# EMGPreamp_extRefv4.net
KiCad netlist of a schematic drawn in EAGLE
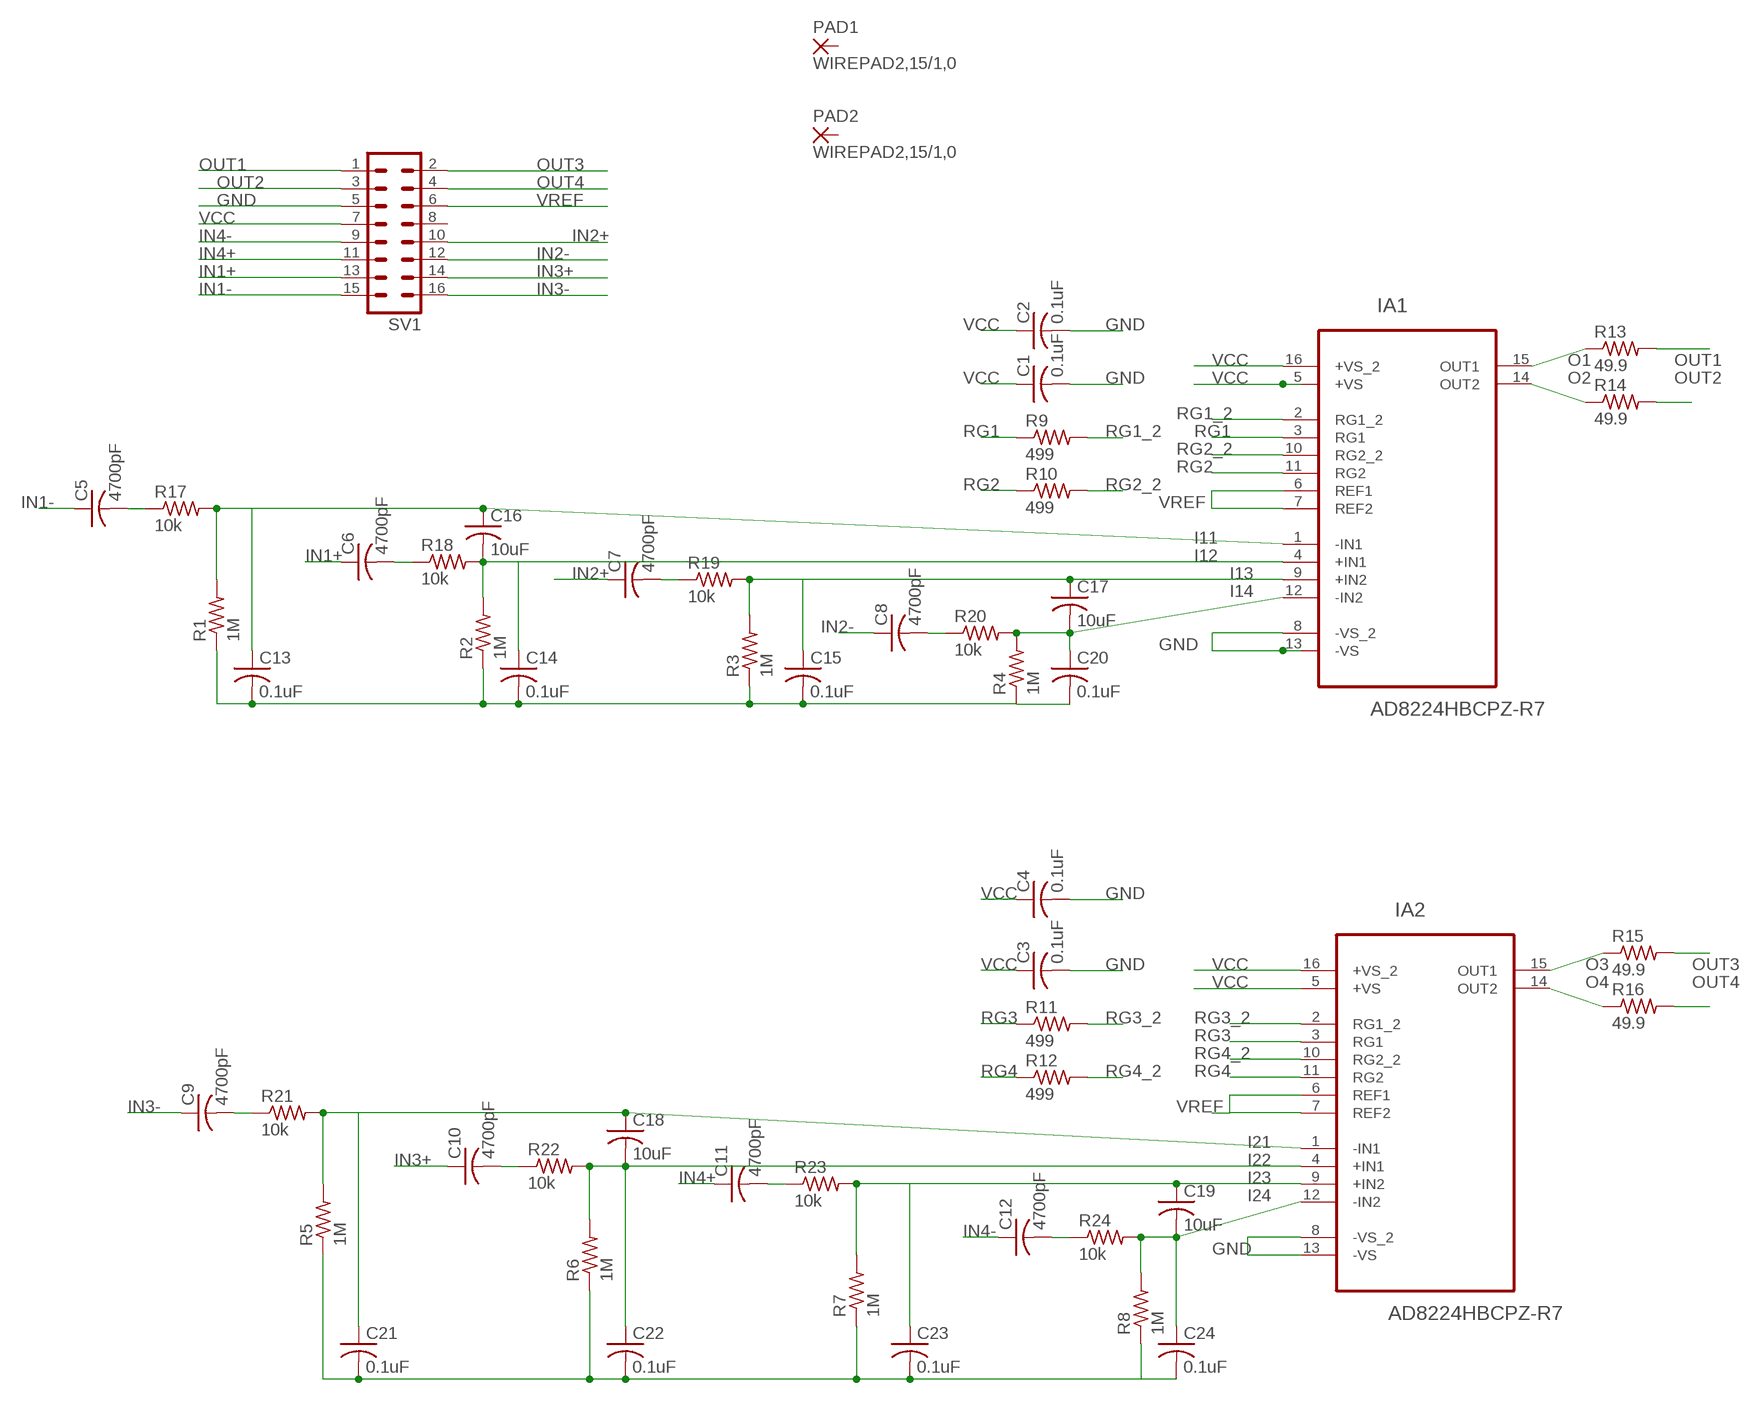
[diagram p0: schematic, sheet 1]

(export (version "E")
  (design (tool "Eeschema 10.0.6"))
  (components
    (comp (ref "C1")
      (value "0.1uF")
      (footprint "eagle-import:C0805")
      (libsource (lib "eagle-import") (part "C-USC0805"))
    )
    (comp (ref "C2")
      (value "0.1uF")
      (footprint "eagle-import:C0805")
      (libsource (lib "eagle-import") (part "C-USC0805"))
    )
    (comp (ref "C3")
      (value "0.1uF")
      (footprint "eagle-import:C0805")
      (libsource (lib "eagle-import") (part "C-USC0805"))
    )
    (comp (ref "C4")
      (value "0.1uF")
      (footprint "eagle-import:C0805")
      (libsource (lib "eagle-import") (part "C-USC0805"))
    )
    (comp (ref "C5")
      (value "4700pF")
      (footprint "eagle-import:C0805")
      (libsource (lib "eagle-import") (part "C-USC0805"))
    )
    (comp (ref "C6")
      (value "4700pF")
      (footprint "eagle-import:C0805")
      (libsource (lib "eagle-import") (part "C-USC0805"))
    )
    (comp (ref "C7")
      (value "4700pF")
      (footprint "eagle-import:C0805")
      (libsource (lib "eagle-import") (part "C-USC0805"))
    )
    (comp (ref "C8")
      (value "4700pF")
      (footprint "eagle-import:C0805")
      (libsource (lib "eagle-import") (part "C-USC0805"))
    )
    (comp (ref "C9")
      (value "4700pF")
      (footprint "eagle-import:C0805")
      (libsource (lib "eagle-import") (part "C-USC0805"))
    )
    (comp (ref "C10")
      (value "4700pF")
      (footprint "eagle-import:C0805")
      (libsource (lib "eagle-import") (part "C-USC0805"))
    )
    (comp (ref "C11")
      (value "4700pF")
      (footprint "eagle-import:C0805")
      (libsource (lib "eagle-import") (part "C-USC0805"))
    )
    (comp (ref "C12")
      (value "4700pF")
      (footprint "eagle-import:C0805")
      (libsource (lib "eagle-import") (part "C-USC0805"))
    )
    (comp (ref "C13")
      (value "0.1uF")
      (footprint "eagle-import:C0805")
      (libsource (lib "eagle-import") (part "C-USC0805"))
    )
    (comp (ref "C14")
      (value "0.1uF")
      (footprint "eagle-import:C0805")
      (libsource (lib "eagle-import") (part "C-USC0805"))
    )
    (comp (ref "C15")
      (value "0.1uF")
      (footprint "eagle-import:C0805")
      (libsource (lib "eagle-import") (part "C-USC0805"))
    )
    (comp (ref "C16")
      (value "10uF")
      (footprint "eagle-import:C0805")
      (libsource (lib "eagle-import") (part "resistor_C-USC0805"))
    )
    (comp (ref "C17")
      (value "10uF")
      (footprint "eagle-import:C0805")
      (libsource (lib "eagle-import") (part "resistor_C-USC0805"))
    )
    (comp (ref "C18")
      (value "10uF")
      (footprint "eagle-import:C0805")
      (libsource (lib "eagle-import") (part "resistor_C-USC0805"))
    )
    (comp (ref "C19")
      (value "10uF")
      (footprint "eagle-import:C0805")
      (libsource (lib "eagle-import") (part "resistor_C-USC0805"))
    )
    (comp (ref "C20")
      (value "0.1uF")
      (footprint "eagle-import:C0805")
      (libsource (lib "eagle-import") (part "C-USC0805"))
    )
    (comp (ref "C21")
      (value "0.1uF")
      (footprint "eagle-import:C0805")
      (libsource (lib "eagle-import") (part "C-USC0805"))
    )
    (comp (ref "C22")
      (value "0.1uF")
      (footprint "eagle-import:C0805")
      (libsource (lib "eagle-import") (part "C-USC0805"))
    )
    (comp (ref "C23")
      (value "0.1uF")
      (footprint "eagle-import:C0805")
      (libsource (lib "eagle-import") (part "C-USC0805"))
    )
    (comp (ref "C24")
      (value "0.1uF")
      (footprint "eagle-import:C0805")
      (libsource (lib "eagle-import") (part "C-USC0805"))
    )
    (comp (ref "IA1")
      (value "AD8224HBCPZ-R7")
      (footprint "eagle-import:QFN65P400X400X100-16N")
      (libsource (lib "eagle-import") (part "AD8224HBCPZ-R7"))
    )
    (comp (ref "IA2")
      (value "AD8224HBCPZ-R7")
      (footprint "eagle-import:QFN65P400X400X100-16N")
      (libsource (lib "eagle-import") (part "AD8224HBCPZ-R7"))
    )
    (comp (ref "PAD1")
      (value "WIREPAD2,15/1,0")
      (footprint "eagle-import:2,15_1,0")
      (libsource (lib "eagle-import") (part "WIREPAD2,15/1,0"))
    )
    (comp (ref "PAD2")
      (value "WIREPAD2,15/1,0")
      (footprint "eagle-import:2,15_1,0")
      (libsource (lib "eagle-import") (part "WIREPAD2,15/1,0"))
    )
    (comp (ref "R1")
      (value "1M")
      (footprint "eagle-import:R0805")
      (libsource (lib "eagle-import") (part "resistor_R-US_R0805"))
    )
    (comp (ref "R2")
      (value "1M")
      (footprint "eagle-import:R0805")
      (libsource (lib "eagle-import") (part "resistor_R-US_R0805"))
    )
    (comp (ref "R3")
      (value "1M")
      (footprint "eagle-import:R0805")
      (libsource (lib "eagle-import") (part "resistor_R-US_R0805"))
    )
    (comp (ref "R4")
      (value "1M")
      (footprint "eagle-import:R0805")
      (libsource (lib "eagle-import") (part "resistor_R-US_R0805"))
    )
    (comp (ref "R5")
      (value "1M")
      (footprint "eagle-import:R0805")
      (libsource (lib "eagle-import") (part "resistor_R-US_R0805"))
    )
    (comp (ref "R6")
      (value "1M")
      (footprint "eagle-import:R0805")
      (libsource (lib "eagle-import") (part "resistor_R-US_R0805"))
    )
    (comp (ref "R7")
      (value "1M")
      (footprint "eagle-import:R0805")
      (libsource (lib "eagle-import") (part "resistor_R-US_R0805"))
    )
    (comp (ref "R8")
      (value "1M")
      (footprint "eagle-import:R0805")
      (libsource (lib "eagle-import") (part "resistor_R-US_R0805"))
    )
    (comp (ref "R9")
      (value "499")
      (footprint "eagle-import:R0805")
      (libsource (lib "eagle-import") (part "R-US_R0805"))
    )
    (comp (ref "R10")
      (value "499")
      (footprint "eagle-import:R0805")
      (libsource (lib "eagle-import") (part "R-US_R0805"))
    )
    (comp (ref "R11")
      (value "499")
      (footprint "eagle-import:R0805")
      (libsource (lib "eagle-import") (part "R-US_R0805"))
    )
    (comp (ref "R12")
      (value "499")
      (footprint "eagle-import:R0805")
      (libsource (lib "eagle-import") (part "R-US_R0805"))
    )
    (comp (ref "R13")
      (value "49.9")
      (footprint "eagle-import:R0805")
      (libsource (lib "eagle-import") (part "R-US_R0805"))
    )
    (comp (ref "R14")
      (value "49.9")
      (footprint "eagle-import:R0805")
      (libsource (lib "eagle-import") (part "R-US_R0805"))
    )
    (comp (ref "R15")
      (value "49.9")
      (footprint "eagle-import:R0805")
      (libsource (lib "eagle-import") (part "R-US_R0805"))
    )
    (comp (ref "R16")
      (value "49.9")
      (footprint "eagle-import:R0805")
      (libsource (lib "eagle-import") (part "R-US_R0805"))
    )
    (comp (ref "R17")
      (value "10k")
      (footprint "eagle-import:R0805")
      (libsource (lib "eagle-import") (part "resistor_R-US_R0805"))
    )
    (comp (ref "R18")
      (value "10k")
      (footprint "eagle-import:R0805")
      (libsource (lib "eagle-import") (part "resistor_R-US_R0805"))
    )
    (comp (ref "R19")
      (value "10k")
      (footprint "eagle-import:R0805")
      (libsource (lib "eagle-import") (part "resistor_R-US_R0805"))
    )
    (comp (ref "R20")
      (value "10k")
      (footprint "eagle-import:R0805")
      (libsource (lib "eagle-import") (part "resistor_R-US_R0805"))
    )
    (comp (ref "R21")
      (value "10k")
      (footprint "eagle-import:R0805")
      (libsource (lib "eagle-import") (part "resistor_R-US_R0805"))
    )
    (comp (ref "R22")
      (value "10k")
      (footprint "eagle-import:R0805")
      (libsource (lib "eagle-import") (part "resistor_R-US_R0805"))
    )
    (comp (ref "R23")
      (value "10k")
      (footprint "eagle-import:R0805")
      (libsource (lib "eagle-import") (part "resistor_R-US_R0805"))
    )
    (comp (ref "R24")
      (value "10k")
      (footprint "eagle-import:R0805")
      (libsource (lib "eagle-import") (part "resistor_R-US_R0805"))
    )
    (comp (ref "SV1")
      (value "MA08-2W")
      (footprint "eagle-import:MA08-2W")
      (libsource (lib "eagle-import") (part "MA08-2W"))
    )
  )
  (nets
    (net (code "1") (name "/GND") (class "Default")
      (node (ref "C1") (pin "2") (pinfunction "2_2") (pintype "passive"))
      (node (ref "C13") (pin "2") (pinfunction "2_2") (pintype "passive"))
      (node (ref "C14") (pin "2") (pinfunction "2_2") (pintype "passive"))
      (node (ref "C15") (pin "2") (pinfunction "2_2") (pintype "passive"))
      (node (ref "C2") (pin "2") (pinfunction "2_2") (pintype "passive"))
      (node (ref "C20") (pin "2") (pinfunction "2_2") (pintype "passive"))
      (node (ref "C21") (pin "2") (pinfunction "2_2") (pintype "passive"))
      (node (ref "C22") (pin "2") (pinfunction "2_2") (pintype "passive"))
      (node (ref "C23") (pin "2") (pinfunction "2_2") (pintype "passive"))
      (node (ref "C24") (pin "2") (pinfunction "2_2") (pintype "passive"))
      (node (ref "C3") (pin "2") (pinfunction "2_2") (pintype "passive"))
      (node (ref "C4") (pin "2") (pinfunction "2_2") (pintype "passive"))
      (node (ref "IA1") (pin "13") (pinfunction "-VS_13") (pintype "power_in"))
      (node (ref "IA1") (pin "8") (pinfunction "-VS_2_8") (pintype "power_in"))
      (node (ref "IA2") (pin "13") (pinfunction "-VS_13") (pintype "power_in"))
      (node (ref "IA2") (pin "8") (pinfunction "-VS_2_8") (pintype "power_in"))
      (node (ref "R1") (pin "1") (pinfunction "1_1") (pintype "passive"))
      (node (ref "R2") (pin "1") (pinfunction "1_1") (pintype "passive"))
      (node (ref "R3") (pin "1") (pinfunction "1_1") (pintype "passive"))
      (node (ref "R4") (pin "1") (pinfunction "1_1") (pintype "passive"))
      (node (ref "R5") (pin "1") (pinfunction "1_1") (pintype "passive"))
      (node (ref "R6") (pin "1") (pinfunction "1_1") (pintype "passive"))
      (node (ref "R7") (pin "1") (pinfunction "1_1") (pintype "passive"))
      (node (ref "R8") (pin "1") (pinfunction "1_1") (pintype "passive"))
      (node (ref "SV1") (pin "5") (pinfunction "5_5") (pintype "passive"))
    )
    (net (code "2") (name "/I11") (class "Default")
      (node (ref "C13") (pin "1") (pinfunction "1_1") (pintype "passive"))
      (node (ref "C16") (pin "1") (pinfunction "1_1") (pintype "passive"))
      (node (ref "IA1") (pin "1") (pinfunction "-IN1_1") (pintype "input"))
      (node (ref "R1") (pin "2") (pinfunction "2_2") (pintype "passive"))
      (node (ref "R17") (pin "2") (pinfunction "2_2") (pintype "passive"))
    )
    (net (code "3") (name "/I12") (class "Default")
      (node (ref "C14") (pin "1") (pinfunction "1_1") (pintype "passive"))
      (node (ref "C16") (pin "2") (pinfunction "2_2") (pintype "passive"))
      (node (ref "IA1") (pin "4") (pinfunction "+IN1_4") (pintype "input"))
      (node (ref "R18") (pin "2") (pinfunction "2_2") (pintype "passive"))
      (node (ref "R2") (pin "2") (pinfunction "2_2") (pintype "passive"))
    )
    (net (code "4") (name "/I13") (class "Default")
      (node (ref "C15") (pin "1") (pinfunction "1_1") (pintype "passive"))
      (node (ref "C17") (pin "1") (pinfunction "1_1") (pintype "passive"))
      (node (ref "IA1") (pin "9") (pinfunction "+IN2_9") (pintype "input"))
      (node (ref "R19") (pin "2") (pinfunction "2_2") (pintype "passive"))
      (node (ref "R3") (pin "2") (pinfunction "2_2") (pintype "passive"))
    )
    (net (code "5") (name "/I14") (class "Default")
      (node (ref "C17") (pin "2") (pinfunction "2_2") (pintype "passive"))
      (node (ref "C20") (pin "1") (pinfunction "1_1") (pintype "passive"))
      (node (ref "IA1") (pin "12") (pinfunction "-IN2_12") (pintype "input"))
      (node (ref "R20") (pin "2") (pinfunction "2_2") (pintype "passive"))
      (node (ref "R4") (pin "2") (pinfunction "2_2") (pintype "passive"))
    )
    (net (code "6") (name "/I21") (class "Default")
      (node (ref "C18") (pin "1") (pinfunction "1_1") (pintype "passive"))
      (node (ref "C21") (pin "1") (pinfunction "1_1") (pintype "passive"))
      (node (ref "IA2") (pin "1") (pinfunction "-IN1_1") (pintype "input"))
      (node (ref "R21") (pin "2") (pinfunction "2_2") (pintype "passive"))
      (node (ref "R5") (pin "2") (pinfunction "2_2") (pintype "passive"))
    )
    (net (code "7") (name "/I22") (class "Default")
      (node (ref "C18") (pin "2") (pinfunction "2_2") (pintype "passive"))
      (node (ref "C22") (pin "1") (pinfunction "1_1") (pintype "passive"))
      (node (ref "IA2") (pin "4") (pinfunction "+IN1_4") (pintype "input"))
      (node (ref "R22") (pin "2") (pinfunction "2_2") (pintype "passive"))
      (node (ref "R6") (pin "2") (pinfunction "2_2") (pintype "passive"))
    )
    (net (code "8") (name "/I23") (class "Default")
      (node (ref "C19") (pin "1") (pinfunction "1_1") (pintype "passive"))
      (node (ref "C23") (pin "1") (pinfunction "1_1") (pintype "passive"))
      (node (ref "IA2") (pin "9") (pinfunction "+IN2_9") (pintype "input"))
      (node (ref "R23") (pin "2") (pinfunction "2_2") (pintype "passive"))
      (node (ref "R7") (pin "2") (pinfunction "2_2") (pintype "passive"))
    )
    (net (code "9") (name "/I24") (class "Default")
      (node (ref "C19") (pin "2") (pinfunction "2_2") (pintype "passive"))
      (node (ref "C24") (pin "1") (pinfunction "1_1") (pintype "passive"))
      (node (ref "IA2") (pin "12") (pinfunction "-IN2_12") (pintype "input"))
      (node (ref "R24") (pin "2") (pinfunction "2_2") (pintype "passive"))
      (node (ref "R8") (pin "2") (pinfunction "2_2") (pintype "passive"))
    )
    (net (code "10") (name "/IN1+") (class "Default")
      (node (ref "C6") (pin "1") (pinfunction "1_1") (pintype "passive"))
      (node (ref "SV1") (pin "13") (pinfunction "13_13") (pintype "passive"))
    )
    (net (code "11") (name "/IN1-") (class "Default")
      (node (ref "C5") (pin "1") (pinfunction "1_1") (pintype "passive"))
      (node (ref "SV1") (pin "15") (pinfunction "15_15") (pintype "passive"))
    )
    (net (code "12") (name "/IN2+") (class "Default")
      (node (ref "C7") (pin "1") (pinfunction "1_1") (pintype "passive"))
      (node (ref "SV1") (pin "10") (pinfunction "10_10") (pintype "passive"))
    )
    (net (code "13") (name "/IN2-") (class "Default")
      (node (ref "C8") (pin "1") (pinfunction "1_1") (pintype "passive"))
      (node (ref "SV1") (pin "12") (pinfunction "12_12") (pintype "passive"))
    )
    (net (code "14") (name "/IN3+") (class "Default")
      (node (ref "C10") (pin "1") (pinfunction "1_1") (pintype "passive"))
      (node (ref "SV1") (pin "14") (pinfunction "14_14") (pintype "passive"))
    )
    (net (code "15") (name "/IN3-") (class "Default")
      (node (ref "C9") (pin "1") (pinfunction "1_1") (pintype "passive"))
      (node (ref "SV1") (pin "16") (pinfunction "16_16") (pintype "passive"))
    )
    (net (code "16") (name "/IN4+") (class "Default")
      (node (ref "C11") (pin "1") (pinfunction "1_1") (pintype "passive"))
      (node (ref "SV1") (pin "11") (pinfunction "11_11") (pintype "passive"))
    )
    (net (code "17") (name "/IN4-") (class "Default")
      (node (ref "C12") (pin "1") (pinfunction "1_1") (pintype "passive"))
      (node (ref "SV1") (pin "9") (pinfunction "9_9") (pintype "passive"))
    )
    (net (code "18") (name "/O1") (class "Default")
      (node (ref "IA1") (pin "15") (pinfunction "OUT1_15") (pintype "output"))
      (node (ref "R13") (pin "1") (pinfunction "1_1") (pintype "passive"))
    )
    (net (code "19") (name "/O2") (class "Default")
      (node (ref "IA1") (pin "14") (pinfunction "OUT2_14") (pintype "output"))
      (node (ref "R14") (pin "1") (pinfunction "1_1") (pintype "passive"))
    )
    (net (code "20") (name "/O3") (class "Default")
      (node (ref "IA2") (pin "15") (pinfunction "OUT1_15") (pintype "output"))
      (node (ref "R15") (pin "1") (pinfunction "1_1") (pintype "passive"))
    )
    (net (code "21") (name "/O4") (class "Default")
      (node (ref "IA2") (pin "14") (pinfunction "OUT2_14") (pintype "output"))
      (node (ref "R16") (pin "1") (pinfunction "1_1") (pintype "passive"))
    )
    (net (code "22") (name "/OUT1") (class "Default")
      (node (ref "R13") (pin "2") (pinfunction "2_2") (pintype "passive"))
      (node (ref "SV1") (pin "1") (pinfunction "1_1") (pintype "passive"))
    )
    (net (code "23") (name "/OUT2") (class "Default")
      (node (ref "R14") (pin "2") (pinfunction "2_2") (pintype "passive"))
      (node (ref "SV1") (pin "3") (pinfunction "3_3") (pintype "passive"))
    )
    (net (code "24") (name "/OUT3") (class "Default")
      (node (ref "R15") (pin "2") (pinfunction "2_2") (pintype "passive"))
      (node (ref "SV1") (pin "2") (pinfunction "2_2") (pintype "passive"))
    )
    (net (code "25") (name "/OUT4") (class "Default")
      (node (ref "R16") (pin "2") (pinfunction "2_2") (pintype "passive"))
      (node (ref "SV1") (pin "4") (pinfunction "4_4") (pintype "passive"))
    )
    (net (code "26") (name "/RG1") (class "Default")
      (node (ref "IA1") (pin "3") (pinfunction "RG1_3") (pintype "passive"))
      (node (ref "R9") (pin "1") (pinfunction "1_1") (pintype "passive"))
    )
    (net (code "27") (name "/RG1_2") (class "Default")
      (node (ref "IA1") (pin "2") (pinfunction "RG1_2_2") (pintype "passive"))
      (node (ref "R9") (pin "2") (pinfunction "2_2") (pintype "passive"))
    )
    (net (code "28") (name "/RG2") (class "Default")
      (node (ref "IA1") (pin "11") (pinfunction "RG2_11") (pintype "passive"))
      (node (ref "R10") (pin "1") (pinfunction "1_1") (pintype "passive"))
    )
    (net (code "29") (name "/RG2_2") (class "Default")
      (node (ref "IA1") (pin "10") (pinfunction "RG2_2_10") (pintype "passive"))
      (node (ref "R10") (pin "2") (pinfunction "2_2") (pintype "passive"))
    )
    (net (code "30") (name "/RG3") (class "Default")
      (node (ref "IA2") (pin "3") (pinfunction "RG1_3") (pintype "passive"))
      (node (ref "R11") (pin "1") (pinfunction "1_1") (pintype "passive"))
    )
    (net (code "31") (name "/RG3_2") (class "Default")
      (node (ref "IA2") (pin "2") (pinfunction "RG1_2_2") (pintype "passive"))
      (node (ref "R11") (pin "2") (pinfunction "2_2") (pintype "passive"))
    )
    (net (code "32") (name "/RG4") (class "Default")
      (node (ref "IA2") (pin "11") (pinfunction "RG2_11") (pintype "passive"))
      (node (ref "R12") (pin "1") (pinfunction "1_1") (pintype "passive"))
    )
    (net (code "33") (name "/RG4_2") (class "Default")
      (node (ref "IA2") (pin "10") (pinfunction "RG2_2_10") (pintype "passive"))
      (node (ref "R12") (pin "2") (pinfunction "2_2") (pintype "passive"))
    )
    (net (code "34") (name "/VCC") (class "Default")
      (node (ref "C1") (pin "1") (pinfunction "1_1") (pintype "passive"))
      (node (ref "C2") (pin "1") (pinfunction "1_1") (pintype "passive"))
      (node (ref "C3") (pin "1") (pinfunction "1_1") (pintype "passive"))
      (node (ref "C4") (pin "1") (pinfunction "1_1") (pintype "passive"))
      (node (ref "IA1") (pin "16") (pinfunction "+VS_2_16") (pintype "power_in"))
      (node (ref "IA1") (pin "5") (pinfunction "+VS_5") (pintype "power_in"))
      (node (ref "IA2") (pin "16") (pinfunction "+VS_2_16") (pintype "power_in"))
      (node (ref "IA2") (pin "5") (pinfunction "+VS_5") (pintype "power_in"))
      (node (ref "SV1") (pin "7") (pinfunction "7_7") (pintype "passive"))
    )
    (net (code "35") (name "/VREF") (class "Default")
      (node (ref "IA1") (pin "6") (pinfunction "REF1_6") (pintype "input"))
      (node (ref "IA1") (pin "7") (pinfunction "REF2_7") (pintype "input"))
      (node (ref "IA2") (pin "6") (pinfunction "REF1_6") (pintype "input"))
      (node (ref "IA2") (pin "7") (pinfunction "REF2_7") (pintype "input"))
      (node (ref "SV1") (pin "6") (pinfunction "6_6") (pintype "passive"))
    )
    (net (code "36") (name "Net-(C5-Pad2)") (class "Default")
      (node (ref "C5") (pin "2") (pinfunction "2_2") (pintype "passive"))
      (node (ref "R17") (pin "1") (pinfunction "1_1") (pintype "passive"))
    )
    (net (code "37") (name "Net-(C6-Pad2)") (class "Default")
      (node (ref "C6") (pin "2") (pinfunction "2_2") (pintype "passive"))
      (node (ref "R18") (pin "1") (pinfunction "1_1") (pintype "passive"))
    )
    (net (code "38") (name "Net-(C7-Pad2)") (class "Default")
      (node (ref "C7") (pin "2") (pinfunction "2_2") (pintype "passive"))
      (node (ref "R19") (pin "1") (pinfunction "1_1") (pintype "passive"))
    )
    (net (code "39") (name "Net-(C8-Pad2)") (class "Default")
      (node (ref "C8") (pin "2") (pinfunction "2_2") (pintype "passive"))
      (node (ref "R20") (pin "1") (pinfunction "1_1") (pintype "passive"))
    )
    (net (code "40") (name "Net-(C9-Pad2)") (class "Default")
      (node (ref "C9") (pin "2") (pinfunction "2_2") (pintype "passive"))
      (node (ref "R21") (pin "1") (pinfunction "1_1") (pintype "passive"))
    )
    (net (code "41") (name "Net-(C10-Pad2)") (class "Default")
      (node (ref "C10") (pin "2") (pinfunction "2_2") (pintype "passive"))
      (node (ref "R22") (pin "1") (pinfunction "1_1") (pintype "passive"))
    )
    (net (code "42") (name "Net-(C11-Pad2)") (class "Default")
      (node (ref "C11") (pin "2") (pinfunction "2_2") (pintype "passive"))
      (node (ref "R23") (pin "1") (pinfunction "1_1") (pintype "passive"))
    )
    (net (code "43") (name "Net-(C12-Pad2)") (class "Default")
      (node (ref "C12") (pin "2") (pinfunction "2_2") (pintype "passive"))
      (node (ref "R24") (pin "1") (pinfunction "1_1") (pintype "passive"))
    )
    (net (code "44") (name "unconnected-(PAD1-P-Pad1)") (class "Default")
      (node (ref "PAD1") (pin "1") (pinfunction "P_1") (pintype "passive"))
    )
    (net (code "45") (name "unconnected-(PAD2-P-Pad1)") (class "Default")
      (node (ref "PAD2") (pin "1") (pinfunction "P_1") (pintype "passive"))
    )
    (net (code "46") (name "unconnected-(SV1-Pad8)") (class "Default")
      (node (ref "SV1") (pin "8") (pinfunction "8_8") (pintype "passive"))
    )
  )
)
